# DriverControlsCarrierBoardMezzanine.net
KiCad netlist of a schematic drawn in Altium Designer
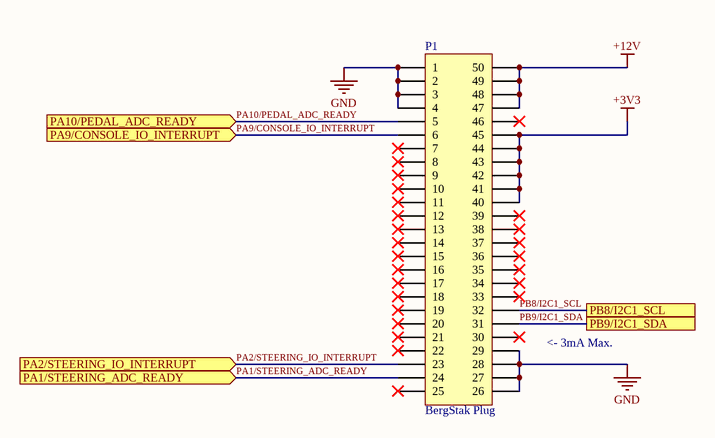
[diagram p0: DriverControlsCarrierBoardMezzanine.SchDoc]

(export (version "E")
  (design (tool "Eeschema 10.0.6"))
  (components
    (comp (ref "P1")
      (value "CONN 50POS Bergstak Plug 0.02\"")
      (footprint "CONN, Bergstak 50 Pos Plug")
      (description "50 Position Connector Plug, Outer Shroud Contacts Surface Mount Gold")
      (fields (field (name "SERIES") "BergStak Plug"))
      (libsource (lib "Schematic Diagrams") (part "CONN 50POS Bergstak Plug 0.02{dblquote}"))
    )
  )
  (nets
    (net (code "1") (name "+3V3") (class "Default")
      (node (ref "P1") (pin "40") (pinfunction "40_40") (pintype "passive"))
      (node (ref "P1") (pin "41") (pinfunction "41_41") (pintype "passive"))
      (node (ref "P1") (pin "42") (pinfunction "42_42") (pintype "passive"))
      (node (ref "P1") (pin "43") (pinfunction "43_43") (pintype "passive"))
      (node (ref "P1") (pin "44") (pinfunction "44_44") (pintype "passive"))
      (node (ref "P1") (pin "45") (pinfunction "45_45") (pintype "passive"))
    )
    (net (code "2") (name "+12V") (class "Default")
      (node (ref "P1") (pin "47") (pinfunction "47_47") (pintype "passive"))
      (node (ref "P1") (pin "48") (pinfunction "48_48") (pintype "passive"))
      (node (ref "P1") (pin "49") (pinfunction "49_49") (pintype "passive"))
      (node (ref "P1") (pin "50") (pinfunction "50_50") (pintype "passive"))
    )
    (net (code "3") (name "/PA1{slash}STEERING_ADC_READY") (class "Default")
      (node (ref "P1") (pin "24") (pinfunction "24_24") (pintype "passive"))
    )
    (net (code "4") (name "/PA2{slash}STEERING_IO_INTERRUPT") (class "Default")
      (node (ref "P1") (pin "23") (pinfunction "23_23") (pintype "passive"))
    )
    (net (code "5") (name "/PA9{slash}CONSOLE_IO_INTERRUPT") (class "Default")
      (node (ref "P1") (pin "6") (pinfunction "6_6") (pintype "passive"))
    )
    (net (code "6") (name "/PA10{slash}PEDAL_ADC_READY") (class "Default")
      (node (ref "P1") (pin "5") (pinfunction "5_5") (pintype "passive"))
    )
    (net (code "7") (name "/PB8{slash}I2C1_SCL") (class "Default")
      (node (ref "P1") (pin "32") (pinfunction "32_32") (pintype "passive"))
    )
    (net (code "8") (name "/PB9{slash}I2C1_SDA") (class "Default")
      (node (ref "P1") (pin "31") (pinfunction "31_31") (pintype "passive"))
    )
    (net (code "9") (name "GND") (class "Default")
      (node (ref "P1") (pin "1") (pinfunction "1_1") (pintype "passive"))
      (node (ref "P1") (pin "2") (pinfunction "2_2") (pintype "passive"))
      (node (ref "P1") (pin "26") (pinfunction "26_26") (pintype "passive"))
      (node (ref "P1") (pin "27") (pinfunction "27_27") (pintype "passive"))
      (node (ref "P1") (pin "28") (pinfunction "28_28") (pintype "passive"))
      (node (ref "P1") (pin "29") (pinfunction "29_29") (pintype "passive"))
      (node (ref "P1") (pin "3") (pinfunction "3_3") (pintype "passive"))
      (node (ref "P1") (pin "4") (pinfunction "4_4") (pintype "passive"))
    )
    (net (code "10") (name "unconnected-(P1-Pad7)") (class "Default")
      (node (ref "P1") (pin "7") (pinfunction "7_7") (pintype "passive+no_connect"))
    )
    (net (code "11") (name "unconnected-(P1-Pad8)") (class "Default")
      (node (ref "P1") (pin "8") (pinfunction "8_8") (pintype "passive+no_connect"))
    )
    (net (code "12") (name "unconnected-(P1-Pad9)") (class "Default")
      (node (ref "P1") (pin "9") (pinfunction "9_9") (pintype "passive+no_connect"))
    )
    (net (code "13") (name "unconnected-(P1-Pad10)") (class "Default")
      (node (ref "P1") (pin "10") (pinfunction "10_10") (pintype "passive+no_connect"))
    )
    (net (code "14") (name "unconnected-(P1-Pad11)") (class "Default")
      (node (ref "P1") (pin "11") (pinfunction "11_11") (pintype "passive+no_connect"))
    )
    (net (code "15") (name "unconnected-(P1-Pad12)") (class "Default")
      (node (ref "P1") (pin "12") (pinfunction "12_12") (pintype "passive+no_connect"))
    )
    (net (code "16") (name "unconnected-(P1-Pad13)") (class "Default")
      (node (ref "P1") (pin "13") (pinfunction "13_13") (pintype "passive+no_connect"))
    )
    (net (code "17") (name "unconnected-(P1-Pad14)") (class "Default")
      (node (ref "P1") (pin "14") (pinfunction "14_14") (pintype "passive+no_connect"))
    )
    (net (code "18") (name "unconnected-(P1-Pad15)") (class "Default")
      (node (ref "P1") (pin "15") (pinfunction "15_15") (pintype "passive+no_connect"))
    )
    (net (code "19") (name "unconnected-(P1-Pad16)") (class "Default")
      (node (ref "P1") (pin "16") (pinfunction "16_16") (pintype "passive+no_connect"))
    )
    (net (code "20") (name "unconnected-(P1-Pad17)") (class "Default")
      (node (ref "P1") (pin "17") (pinfunction "17_17") (pintype "passive+no_connect"))
    )
    (net (code "21") (name "unconnected-(P1-Pad18)") (class "Default")
      (node (ref "P1") (pin "18") (pinfunction "18_18") (pintype "passive+no_connect"))
    )
    (net (code "22") (name "unconnected-(P1-Pad19)") (class "Default")
      (node (ref "P1") (pin "19") (pinfunction "19_19") (pintype "passive+no_connect"))
    )
    (net (code "23") (name "unconnected-(P1-Pad20)") (class "Default")
      (node (ref "P1") (pin "20") (pinfunction "20_20") (pintype "passive+no_connect"))
    )
    (net (code "24") (name "unconnected-(P1-Pad21)") (class "Default")
      (node (ref "P1") (pin "21") (pinfunction "21_21") (pintype "passive+no_connect"))
    )
    (net (code "25") (name "unconnected-(P1-Pad22)") (class "Default")
      (node (ref "P1") (pin "22") (pinfunction "22_22") (pintype "passive+no_connect"))
    )
    (net (code "26") (name "unconnected-(P1-Pad25)") (class "Default")
      (node (ref "P1") (pin "25") (pinfunction "25_25") (pintype "passive+no_connect"))
    )
    (net (code "27") (name "unconnected-(P1-Pad30)") (class "Default")
      (node (ref "P1") (pin "30") (pinfunction "30_30") (pintype "passive+no_connect"))
    )
    (net (code "28") (name "unconnected-(P1-Pad33)") (class "Default")
      (node (ref "P1") (pin "33") (pinfunction "33_33") (pintype "passive+no_connect"))
    )
    (net (code "29") (name "unconnected-(P1-Pad34)") (class "Default")
      (node (ref "P1") (pin "34") (pinfunction "34_34") (pintype "passive+no_connect"))
    )
    (net (code "30") (name "unconnected-(P1-Pad35)") (class "Default")
      (node (ref "P1") (pin "35") (pinfunction "35_35") (pintype "passive+no_connect"))
    )
    (net (code "31") (name "unconnected-(P1-Pad36)") (class "Default")
      (node (ref "P1") (pin "36") (pinfunction "36_36") (pintype "passive+no_connect"))
    )
    (net (code "32") (name "unconnected-(P1-Pad37)") (class "Default")
      (node (ref "P1") (pin "37") (pinfunction "37_37") (pintype "passive+no_connect"))
    )
    (net (code "33") (name "unconnected-(P1-Pad38)") (class "Default")
      (node (ref "P1") (pin "38") (pinfunction "38_38") (pintype "passive+no_connect"))
    )
    (net (code "34") (name "unconnected-(P1-Pad39)") (class "Default")
      (node (ref "P1") (pin "39") (pinfunction "39_39") (pintype "passive+no_connect"))
    )
    (net (code "35") (name "unconnected-(P1-Pad46)") (class "Default")
      (node (ref "P1") (pin "46") (pinfunction "46_46") (pintype "passive+no_connect"))
    )
  )
)
